# log-controller-v2.net
KiCad netlist of a schematic drawn in EAGLE
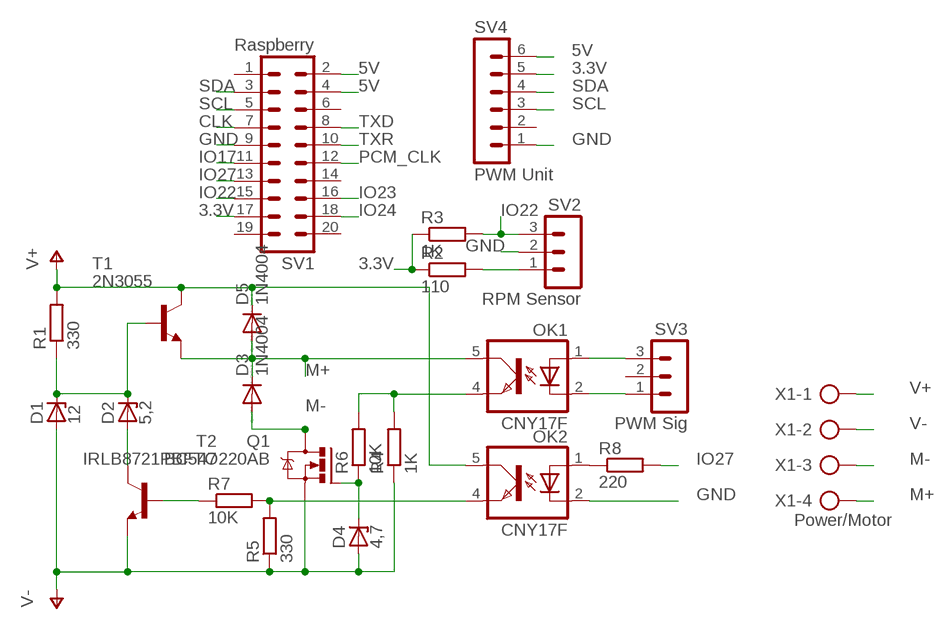
[diagram p0: schematic, sheet 1]

(export (version "E")
  (design (tool "Eeschema 10.0.6"))
  (components
    (comp (ref "D1")
      (value "12")
      (footprint "eagle-import:DO34Z7")
      (libsource (lib "eagle-import") (part "BZX90"))
    )
    (comp (ref "D2")
      (value "5,2")
      (footprint "eagle-import:DO34Z7")
      (libsource (lib "eagle-import") (part "BZX90"))
    )
    (comp (ref "D3")
      (value "1N4004")
      (footprint "eagle-import:DO41-10")
      (libsource (lib "eagle-import") (part "1N4004"))
    )
    (comp (ref "D4")
      (value "4,7")
      (footprint "eagle-import:DO34Z7")
      (libsource (lib "eagle-import") (part "BZX90"))
    )
    (comp (ref "D5")
      (value "1N4004")
      (footprint "eagle-import:DO41-10")
      (libsource (lib "eagle-import") (part "1N4004"))
    )
    (comp (ref "OK1")
      (value "CNY17F")
      (footprint "eagle-import:DIL06")
      (fields (field (name "MF") "VISHAY/TELEFUNKEN") (field (name "MPN") "CNY17F-3"))
      (libsource (lib "eagle-import") (part "CNY17F"))
    )
    (comp (ref "OK2")
      (value "CNY17F")
      (footprint "eagle-import:DIL06")
      (fields (field (name "MF") "VISHAY/TELEFUNKEN") (field (name "MPN") "CNY17F-3"))
      (libsource (lib "eagle-import") (part "CNY17F"))
    )
    (comp (ref "Q1")
      (value "IRLB8721PBFTO220AB")
      (footprint "eagle-import:TO220AB")
      (libsource (lib "eagle-import") (part "IRLB8721PBFTO220AB"))
    )
    (comp (ref "R1")
      (value "330")
      (footprint "eagle-import:0207_12")
      (libsource (lib "eagle-import") (part "R-EU_0207/12"))
    )
    (comp (ref "R2")
      (value "110")
      (footprint "eagle-import:0207_10")
      (libsource (lib "eagle-import") (part "R-EU_0207/10"))
    )
    (comp (ref "R3")
      (value "1K")
      (footprint "eagle-import:0207_10")
      (libsource (lib "eagle-import") (part "R-EU_0207/10"))
    )
    (comp (ref "R4")
      (value "1K")
      (footprint "eagle-import:0207_12")
      (libsource (lib "eagle-import") (part "R-EU_0207/12"))
    )
    (comp (ref "R5")
      (value "330")
      (footprint "eagle-import:0207_12")
      (libsource (lib "eagle-import") (part "R-EU_0207/12"))
    )
    (comp (ref "R6")
      (value "10K")
      (footprint "eagle-import:0207_12")
      (libsource (lib "eagle-import") (part "R-EU_0207/12"))
    )
    (comp (ref "R7")
      (value "10K")
      (footprint "eagle-import:0207_12")
      (libsource (lib "eagle-import") (part "R-EU_0207/12"))
    )
    (comp (ref "R8")
      (value "220")
      (footprint "eagle-import:0207_10")
      (libsource (lib "eagle-import") (part "R-EU_0207/10"))
    )
    (comp (ref "SV1")
      (value "Raspberry")
      (footprint "eagle-import:MA10-2")
      (libsource (lib "eagle-import") (part "MA10-2"))
    )
    (comp (ref "SV2")
      (value "RPM Sensor")
      (footprint "eagle-import:MA03-1")
      (libsource (lib "eagle-import") (part "MA03-1"))
    )
    (comp (ref "SV3")
      (value "PWM Sig")
      (footprint "eagle-import:MA03-1")
      (libsource (lib "eagle-import") (part "MA03-1"))
    )
    (comp (ref "SV4")
      (value "PWM Unit")
      (footprint "eagle-import:MA06-1")
      (libsource (lib "eagle-import") (part "MA06-1"))
    )
    (comp (ref "T1")
      (value "2N3055")
      (footprint "eagle-import:TO3")
      (libsource (lib "eagle-import") (part "2N3055"))
    )
    (comp (ref "T2")
      (value "BC547")
      (footprint "eagle-import:TO92")
      (libsource (lib "eagle-import") (part "BC547"))
    )
    (comp (ref "X1")
      (value "Power/Motor")
      (footprint "eagle-import:AK300_4")
      (libsource (lib "eagle-import") (part "AK300/4"))
    )
  )
  (nets
    (net (code "1") (name "/3.3V") (class "Default")
      (node (ref "R2") (pin "1") (pinfunction "1_1") (pintype "passive"))
      (node (ref "R3") (pin "1") (pinfunction "1_1") (pintype "passive"))
      (node (ref "SV1") (pin "17") (pinfunction "17_17") (pintype "passive"))
      (node (ref "SV4") (pin "5") (pinfunction "5_5") (pintype "passive"))
    )
    (net (code "2") (name "/5V") (class "Default")
      (node (ref "SV1") (pin "2") (pinfunction "2_2") (pintype "passive"))
      (node (ref "SV1") (pin "4") (pinfunction "4_4") (pintype "passive"))
      (node (ref "SV4") (pin "6") (pinfunction "6_6") (pintype "passive"))
    )
    (net (code "3") (name "/CLK") (class "Default")
      (node (ref "SV1") (pin "7") (pinfunction "7_7") (pintype "passive"))
    )
    (net (code "4") (name "/GND") (class "Default")
      (node (ref "OK2") (pin "2") (pinfunction "C_2") (pintype "passive"))
      (node (ref "SV1") (pin "9") (pinfunction "9_9") (pintype "passive"))
      (node (ref "SV2") (pin "2") (pinfunction "2_2") (pintype "passive"))
      (node (ref "SV4") (pin "1") (pinfunction "1_1") (pintype "passive"))
    )
    (net (code "5") (name "/IO17") (class "Default")
      (node (ref "SV1") (pin "11") (pinfunction "11_11") (pintype "passive"))
    )
    (net (code "6") (name "/IO22") (class "Default")
      (node (ref "R3") (pin "2") (pinfunction "2_2") (pintype "passive"))
      (node (ref "SV1") (pin "15") (pinfunction "15_15") (pintype "passive"))
      (node (ref "SV2") (pin "3") (pinfunction "3_3") (pintype "passive"))
    )
    (net (code "7") (name "/IO23") (class "Default")
      (node (ref "SV1") (pin "16") (pinfunction "16_16") (pintype "passive"))
    )
    (net (code "8") (name "/IO24") (class "Default")
      (node (ref "SV1") (pin "18") (pinfunction "18_18") (pintype "passive"))
    )
    (net (code "9") (name "/IO27") (class "Default")
      (node (ref "R8") (pin "2") (pinfunction "2_2") (pintype "passive"))
      (node (ref "SV1") (pin "13") (pinfunction "13_13") (pintype "passive"))
    )
    (net (code "10") (name "/M+") (class "Default")
      (node (ref "D3") (pin "C") (pinfunction "C_C") (pintype "passive"))
      (node (ref "D5") (pin "A") (pinfunction "A_A") (pintype "passive"))
      (node (ref "OK1") (pin "5") (pinfunction "COL_5") (pintype "passive"))
      (node (ref "T1") (pin "E") (pinfunction "E_E") (pintype "passive"))
      (node (ref "X1") (pin "4") (pinfunction "KL_4") (pintype "passive"))
    )
    (net (code "11") (name "/M-") (class "Default")
      (node (ref "D3") (pin "A") (pinfunction "A_A") (pintype "passive"))
      (node (ref "Q1") (pin "D") (pinfunction "D_D") (pintype "passive"))
      (node (ref "X1") (pin "3") (pinfunction "KL_3") (pintype "passive"))
    )
    (net (code "12") (name "/PCM_CLK") (class "Default")
      (node (ref "SV1") (pin "12") (pinfunction "12_12") (pintype "passive"))
    )
    (net (code "13") (name "/SCL") (class "Default")
      (node (ref "SV1") (pin "5") (pinfunction "5_5") (pintype "passive"))
      (node (ref "SV4") (pin "3") (pinfunction "3_3") (pintype "passive"))
    )
    (net (code "14") (name "/SDA") (class "Default")
      (node (ref "SV1") (pin "3") (pinfunction "3_3") (pintype "passive"))
      (node (ref "SV4") (pin "4") (pinfunction "4_4") (pintype "passive"))
    )
    (net (code "15") (name "/TXD") (class "Default")
      (node (ref "SV1") (pin "8") (pinfunction "8_8") (pintype "passive"))
    )
    (net (code "16") (name "/TXR") (class "Default")
      (node (ref "SV1") (pin "10") (pinfunction "10_10") (pintype "passive"))
    )
    (net (code "17") (name "Net-(D1-PadC)") (class "Default")
      (node (ref "D1") (pin "C") (pinfunction "C_C") (pintype "passive"))
      (node (ref "D2") (pin "C") (pinfunction "C_C") (pintype "passive"))
      (node (ref "R1") (pin "1") (pinfunction "1_1") (pintype "passive"))
      (node (ref "T1") (pin "B") (pinfunction "B_B") (pintype "passive"))
    )
    (net (code "18") (name "Net-(D4-PadC)") (class "Default")
      (node (ref "D4") (pin "C") (pinfunction "C_C") (pintype "passive"))
      (node (ref "Q1") (pin "G") (pinfunction "G_G") (pintype "passive"))
      (node (ref "R6") (pin "1") (pinfunction "1_1") (pintype "passive"))
    )
    (net (code "19") (name "Net-(OK1-A)") (class "Default")
      (node (ref "OK1") (pin "1") (pinfunction "A_1") (pintype "passive"))
      (node (ref "SV3") (pin "3") (pinfunction "3_3") (pintype "passive"))
    )
    (net (code "20") (name "Net-(OK1-C)") (class "Default")
      (node (ref "OK1") (pin "2") (pinfunction "C_2") (pintype "passive"))
      (node (ref "SV3") (pin "1") (pinfunction "1_1") (pintype "passive"))
    )
    (net (code "21") (name "Net-(OK1-EMIT)") (class "Default")
      (node (ref "OK1") (pin "4") (pinfunction "EMIT_4") (pintype "passive"))
      (node (ref "R4") (pin "2") (pinfunction "2_2") (pintype "passive"))
      (node (ref "R6") (pin "2") (pinfunction "2_2") (pintype "passive"))
    )
    (net (code "22") (name "Net-(OK2-A)") (class "Default")
      (node (ref "OK2") (pin "1") (pinfunction "A_1") (pintype "passive"))
      (node (ref "R8") (pin "1") (pinfunction "1_1") (pintype "passive"))
    )
    (net (code "23") (name "Net-(OK2-EMIT)") (class "Default")
      (node (ref "OK2") (pin "4") (pinfunction "EMIT_4") (pintype "passive"))
      (node (ref "R5") (pin "2") (pinfunction "2_2") (pintype "passive"))
      (node (ref "R7") (pin "2") (pinfunction "2_2") (pintype "passive"))
    )
    (net (code "24") (name "Net-(R2-Pad2)") (class "Default")
      (node (ref "R2") (pin "2") (pinfunction "2_2") (pintype "passive"))
      (node (ref "SV2") (pin "1") (pinfunction "1_1") (pintype "passive"))
    )
    (net (code "25") (name "Net-(T2-B)") (class "Default")
      (node (ref "R7") (pin "1") (pinfunction "1_1") (pintype "passive"))
      (node (ref "T2") (pin "2") (pinfunction "B_2") (pintype "passive"))
    )
    (net (code "26") (name "Net-(T2-C)") (class "Default")
      (node (ref "D2") (pin "A") (pinfunction "A_A") (pintype "passive"))
      (node (ref "T2") (pin "3") (pinfunction "C_3") (pintype "passive"))
    )
    (net (code "27") (name "V+") (class "Default")
      (node (ref "D5") (pin "C") (pinfunction "C_C") (pintype "passive"))
      (node (ref "OK2") (pin "5") (pinfunction "COL_5") (pintype "passive"))
      (node (ref "R1") (pin "2") (pinfunction "2_2") (pintype "passive"))
      (node (ref "T1") (pin "C") (pinfunction "C_C") (pintype "passive"))
      (node (ref "T1") (pin "C/") (pinfunction "C_C/") (pintype "passive"))
      (node (ref "X1") (pin "1") (pinfunction "KL_1") (pintype "passive"))
    )
    (net (code "28") (name "V-") (class "Default")
      (node (ref "D1") (pin "A") (pinfunction "A_A") (pintype "passive"))
      (node (ref "D4") (pin "A") (pinfunction "A_A") (pintype "passive"))
      (node (ref "Q1") (pin "S") (pinfunction "S_S") (pintype "passive"))
      (node (ref "R4") (pin "1") (pinfunction "1_1") (pintype "passive"))
      (node (ref "R5") (pin "1") (pinfunction "1_1") (pintype "passive"))
      (node (ref "T2") (pin "1") (pinfunction "E_1") (pintype "passive"))
      (node (ref "X1") (pin "2") (pinfunction "KL_2") (pintype "passive"))
    )
    (net (code "29") (name "unconnected-(SV1-Pad1)") (class "Default")
      (node (ref "SV1") (pin "1") (pinfunction "1_1") (pintype "passive"))
    )
    (net (code "30") (name "unconnected-(SV1-Pad6)") (class "Default")
      (node (ref "SV1") (pin "6") (pinfunction "6_6") (pintype "passive"))
    )
    (net (code "31") (name "unconnected-(SV1-Pad14)") (class "Default")
      (node (ref "SV1") (pin "14") (pinfunction "14_14") (pintype "passive"))
    )
    (net (code "32") (name "unconnected-(SV1-Pad19)") (class "Default")
      (node (ref "SV1") (pin "19") (pinfunction "19_19") (pintype "passive"))
    )
    (net (code "33") (name "unconnected-(SV1-Pad20)") (class "Default")
      (node (ref "SV1") (pin "20") (pinfunction "20_20") (pintype "passive"))
    )
    (net (code "34") (name "unconnected-(SV3-Pad2)") (class "Default")
      (node (ref "SV3") (pin "2") (pinfunction "2_2") (pintype "passive"))
    )
    (net (code "35") (name "unconnected-(SV4-Pad2)") (class "Default")
      (node (ref "SV4") (pin "2") (pinfunction "2_2") (pintype "passive"))
    )
  )
)
